# DHJSNoiseConsole.net
KiCad netlist of a schematic drawn in EAGLE
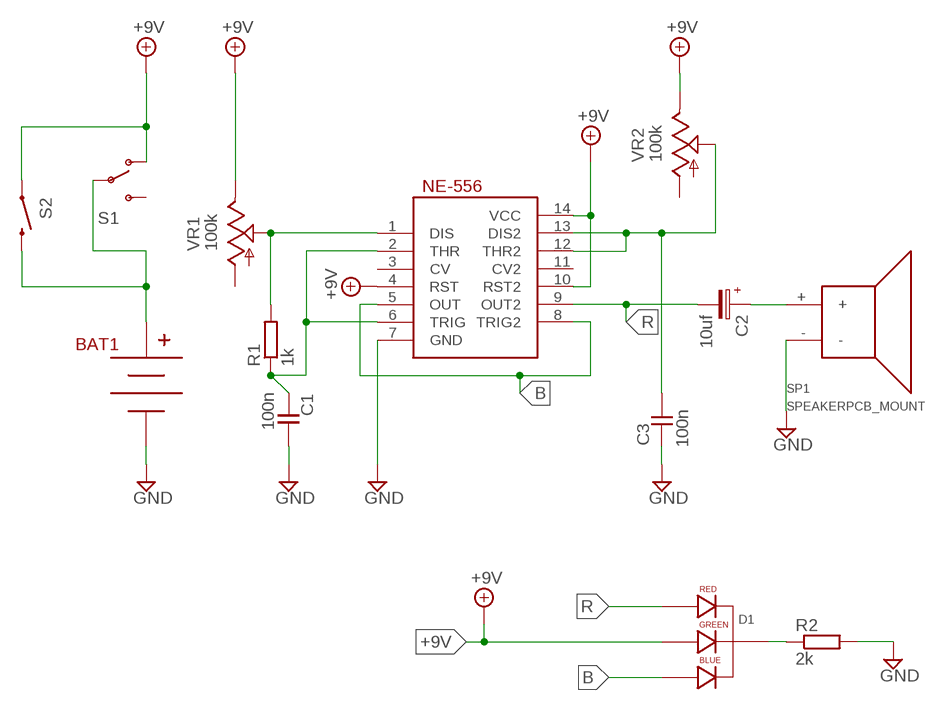
[diagram p0: schematic, sheet 1]

(export (version "E")
  (design (tool "Eeschema 10.0.6"))
  (components
    (comp (ref "BAT1")
      (value "BC9VPC")
      (footprint "eagle-import:BC9VPC")
      (libsource (lib "eagle-import") (part "BC9VPC"))
    )
    (comp (ref "C1")
      (value "100n")
      (footprint "eagle-import:C050-024X044")
      (libsource (lib "eagle-import") (part "C-EU050-024X044"))
    )
    (comp (ref "C2")
      (value "10uf")
      (footprint "eagle-import:050_020")
      (libsource (lib "eagle-import") (part "050-EU"))
    )
    (comp (ref "C3")
      (value "100n")
      (footprint "eagle-import:C050-024X044")
      (libsource (lib "eagle-import") (part "C-EU050-024X044"))
    )
    (comp (ref "D1")
      (value "LED-RGB-CC-THRUCLEAR")
      (footprint "eagle-import:LED-RGB-THRU")
      (libsource (lib "eagle-import") (part "LED-RGB-CC-THRUCLEAR"))
    )
    (comp (ref "NE-556")
      (value "556")
      (footprint "eagle-import:DIL14")
      (libsource (lib "eagle-import") (part "556"))
    )
    (comp (ref "R1")
      (value "1k")
      (footprint "eagle-import:10MM_RESISTOR")
      (libsource (lib "eagle-import") (part "RESISTOR10MM_RESISTOR"))
    )
    (comp (ref "R2")
      (value "2k")
      (footprint "eagle-import:10MM_RESISTOR")
      (libsource (lib "eagle-import") (part "RESISTOR10MM_RESISTOR"))
    )
    (comp (ref "S1")
      (value "SWITCH-SPDTPTH")
      (footprint "eagle-import:SWITCH-SPDT")
      (libsource (lib "eagle-import") (part "SWITCH-SPDTPTH"))
    )
    (comp (ref "S2")
      (value "SWITCH-MOMENTARY-2SIDE_EZ")
      (footprint "eagle-import:TACTILE-PTH-SIDEEZ")
      (libsource (lib "eagle-import") (part "SWITCH-MOMENTARY-2SIDE_EZ"))
    )
    (comp (ref "SP1")
      (value "SPEAKERPCB_MOUNT")
      (footprint "eagle-import:PCB_MOUNT_SPEAKER")
      (fields (field (name "MFG") "SANCO"))
      (libsource (lib "eagle-import") (part "SPEAKERPCB_MOUNT"))
    )
    (comp (ref "VR1")
      (value "100k")
      (footprint "eagle-import:9MM_SNAP-IN_POT")
      (libsource (lib "eagle-import") (part "9MM_SNAP-IN_POT_"))
    )
    (comp (ref "VR2")
      (value "100k")
      (footprint "eagle-import:9MM_SNAP-IN_POT")
      (libsource (lib "eagle-import") (part "9MM_SNAP-IN_POT_"))
    )
  )
  (nets
    (net (code "1") (name "+9V") (class "Default")
      (node (ref "D1") (pin "3") (pinfunction "GREEN_CATHODE_3") (pintype "bidirectional"))
      (node (ref "NE-556") (pin "10") (pinfunction "RST2_10") (pintype "bidirectional"))
      (node (ref "NE-556") (pin "14") (pinfunction "VCC_14") (pintype "bidirectional"))
      (node (ref "NE-556") (pin "4") (pinfunction "RST_4") (pintype "bidirectional"))
      (node (ref "S1") (pin "1") (pinfunction "O_1") (pintype "passive"))
      (node (ref "S2") (pin "1") (pinfunction "1_1") (pintype "passive"))
      (node (ref "VR1") (pin "3") (pinfunction "E_3") (pintype "passive"))
      (node (ref "VR2") (pin "3") (pinfunction "E_3") (pintype "passive"))
    )
    (net (code "2") (name "B") (class "Default")
      (node (ref "D1") (pin "4") (pinfunction "BLUE_CATHODE_4") (pintype "bidirectional"))
      (node (ref "NE-556") (pin "5") (pinfunction "OUT_5") (pintype "bidirectional"))
      (node (ref "NE-556") (pin "8") (pinfunction "TRIG2_8") (pintype "bidirectional"))
    )
    (net (code "3") (name "GND") (class "Default")
      (node (ref "BAT1") (pin "V-") (pinfunction "V-_V-") (pintype "bidirectional"))
      (node (ref "C1") (pin "1") (pinfunction "1_1") (pintype "passive"))
      (node (ref "C3") (pin "2") (pinfunction "2_2") (pintype "passive"))
      (node (ref "NE-556") (pin "7") (pinfunction "GND_7") (pintype "bidirectional"))
      (node (ref "R2") (pin "2") (pinfunction "2_2") (pintype "passive"))
      (node (ref "SP1") (pin "-") (pinfunction "-_-") (pintype "bidirectional"))
    )
    (net (code "4") (name "Net-(C2-Pad+)") (class "Default")
      (node (ref "C2") (pin "+") (pinfunction "+_+") (pintype "passive"))
      (node (ref "SP1") (pin "+") (pinfunction "+_+") (pintype "bidirectional"))
    )
    (net (code "5") (name "Net-(D1-CATHODE)") (class "Default")
      (node (ref "D1") (pin "2") (pinfunction "CATHODE_2") (pintype "bidirectional"))
      (node (ref "R2") (pin "1") (pinfunction "1_1") (pintype "passive"))
    )
    (net (code "6") (name "Net-(NE-556-DIS)") (class "Default")
      (node (ref "NE-556") (pin "1") (pinfunction "DIS_1") (pintype "bidirectional"))
      (node (ref "R1") (pin "2") (pinfunction "2_2") (pintype "passive"))
      (node (ref "VR1") (pin "2") (pinfunction "S_2") (pintype "passive"))
    )
    (net (code "7") (name "Net-(NE-556-DIS2)") (class "Default")
      (node (ref "C3") (pin "1") (pinfunction "1_1") (pintype "passive"))
      (node (ref "NE-556") (pin "12") (pinfunction "THR2_12") (pintype "bidirectional"))
      (node (ref "NE-556") (pin "13") (pinfunction "DIS2_13") (pintype "bidirectional"))
      (node (ref "VR2") (pin "2") (pinfunction "S_2") (pintype "passive"))
    )
    (net (code "8") (name "Net-(NE-556-THR)") (class "Default")
      (node (ref "C1") (pin "2") (pinfunction "2_2") (pintype "passive"))
      (node (ref "NE-556") (pin "2") (pinfunction "THR_2") (pintype "bidirectional"))
      (node (ref "NE-556") (pin "6") (pinfunction "TRIG_6") (pintype "bidirectional"))
      (node (ref "R1") (pin "1") (pinfunction "1_1") (pintype "passive"))
    )
    (net (code "9") (name "Net-(S1-P)") (class "Default")
      (node (ref "BAT1") (pin "V+") (pinfunction "V+_V+") (pintype "bidirectional"))
      (node (ref "S1") (pin "2") (pinfunction "P_2") (pintype "passive"))
      (node (ref "S2") (pin "2") (pinfunction "2_2") (pintype "passive"))
    )
    (net (code "10") (name "R") (class "Default")
      (node (ref "C2") (pin "-") (pinfunction "-_-") (pintype "passive"))
      (node (ref "D1") (pin "1") (pinfunction "RED_CATHODE_1") (pintype "bidirectional"))
      (node (ref "NE-556") (pin "9") (pinfunction "OUT2_9") (pintype "bidirectional"))
    )
    (net (code "11") (name "unconnected-(NE-556-CV-Pad3)") (class "Default")
      (node (ref "NE-556") (pin "3") (pinfunction "CV_3") (pintype "bidirectional"))
    )
    (net (code "12") (name "unconnected-(NE-556-CV2-Pad11)") (class "Default")
      (node (ref "NE-556") (pin "11") (pinfunction "CV2_11") (pintype "bidirectional"))
    )
    (net (code "13") (name "unconnected-(S1-S-Pad3)") (class "Default")
      (node (ref "S1") (pin "3") (pinfunction "S_3") (pintype "passive"))
    )
    (net (code "14") (name "unconnected-(VR1-A-Pad1)") (class "Default")
      (node (ref "VR1") (pin "1") (pinfunction "A_1") (pintype "passive"))
    )
    (net (code "15") (name "unconnected-(VR2-A-Pad1)") (class "Default")
      (node (ref "VR2") (pin "1") (pinfunction "A_1") (pintype "passive"))
    )
  )
)
